# 5_cpu_registers_a.net
KiCad netlist of a schematic drawn in EAGLE
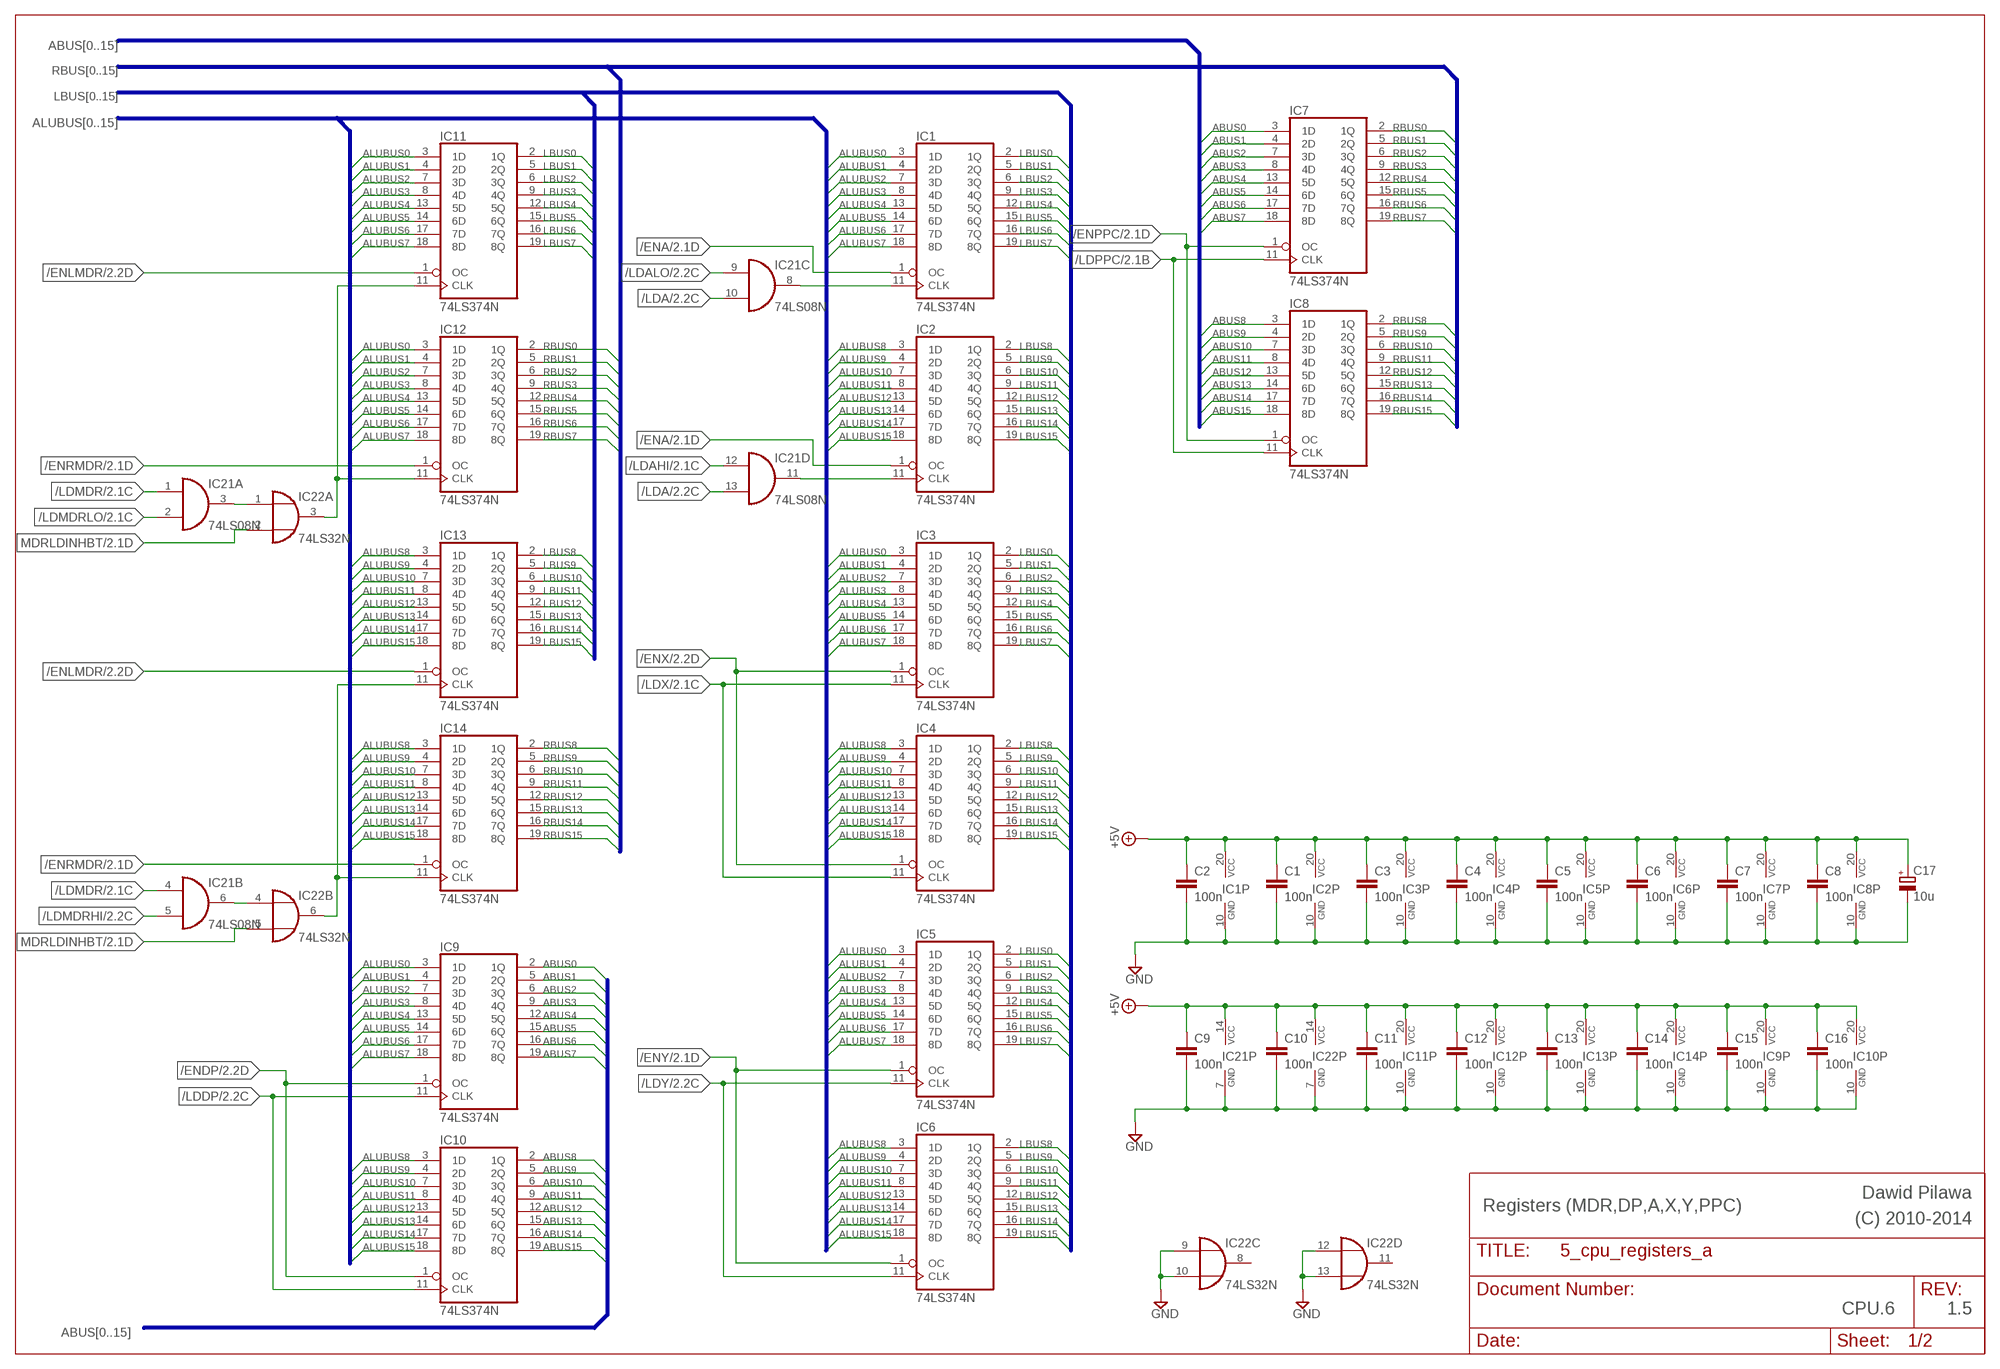
[diagram p0: schematic, sheet 1]
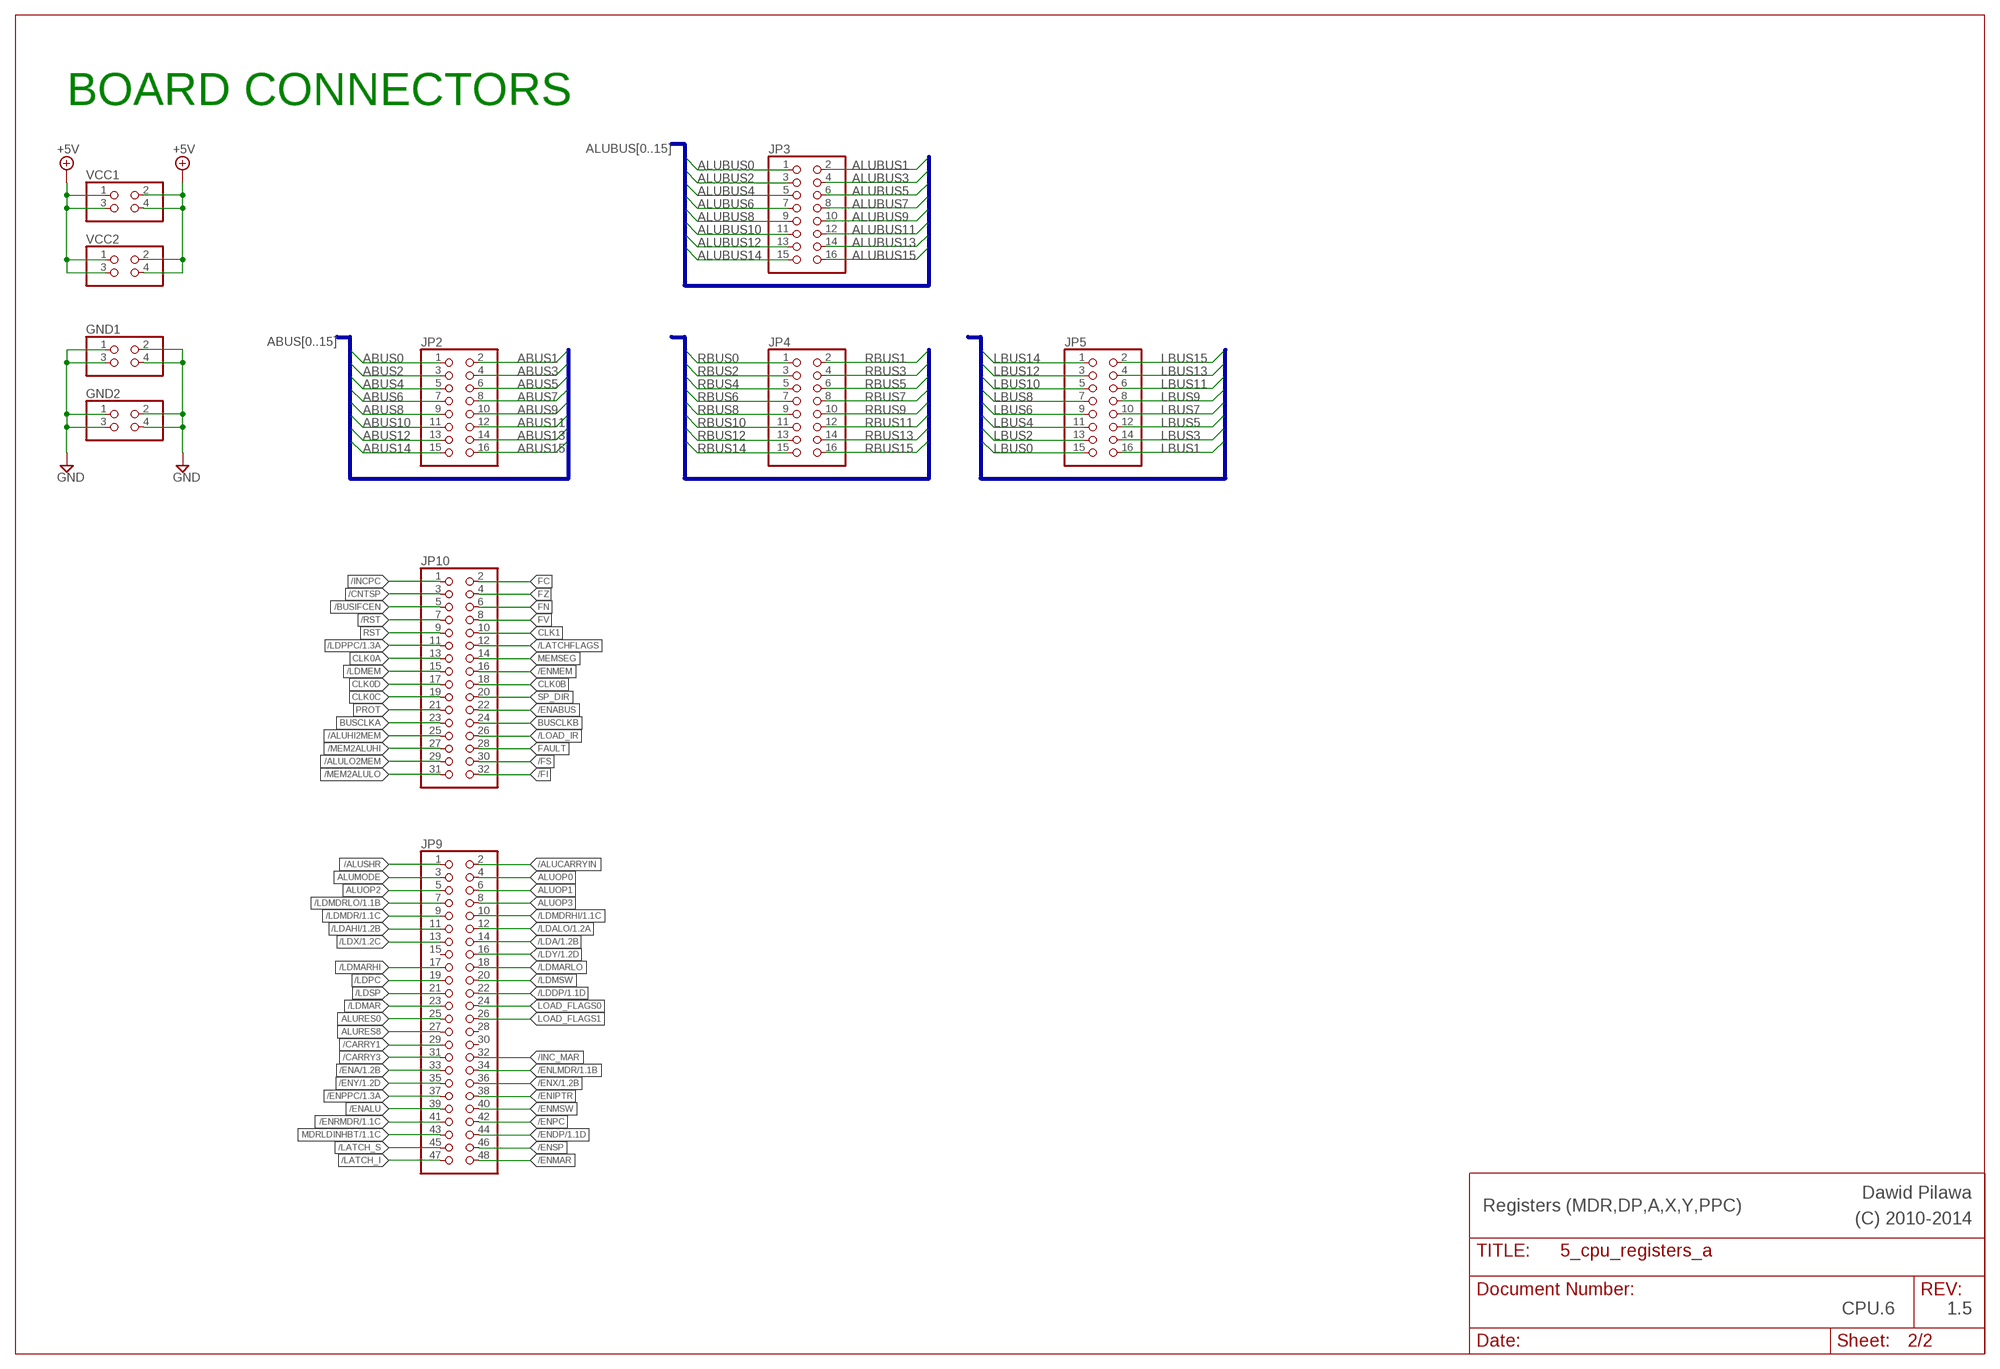
[diagram p1: schematic, sheet 2]

(export (version "E")
  (design (tool "Eeschema 10.0.6"))
  (components
    (comp (ref "GND1")
      (value "PINHD-2X2")
      (footprint "eagle-import:2X02")
      (libsource (lib "eagle-import") (part "PINHD-2X2"))
    )
    (comp (ref "GND2")
      (value "PINHD-2X2")
      (footprint "eagle-import:2X02")
      (libsource (lib "eagle-import") (part "PINHD-2X2"))
    )
    (comp (ref "JP2")
      (value "PINHD-2X8")
      (footprint "eagle-import:2X08")
      (libsource (lib "eagle-import") (part "PINHD-2X8"))
    )
    (comp (ref "JP3")
      (value "PINHD-2X8")
      (footprint "eagle-import:2X08")
      (libsource (lib "eagle-import") (part "PINHD-2X8"))
    )
    (comp (ref "JP4")
      (value "PINHD-2X8")
      (footprint "eagle-import:2X08")
      (libsource (lib "eagle-import") (part "PINHD-2X8"))
    )
    (comp (ref "JP5")
      (value "PINHD-2X8")
      (footprint "eagle-import:2X08")
      (libsource (lib "eagle-import") (part "PINHD-2X8"))
    )
    (comp (ref "JP9")
      (value "PINHD-2X24")
      (footprint "eagle-import:2X24")
      (libsource (lib "eagle-import") (part "PINHD-2X24"))
    )
    (comp (ref "JP10")
      (value "PINHD-2X16")
      (footprint "eagle-import:2X16")
      (libsource (lib "eagle-import") (part "PINHD-2X16"))
    )
    (comp (ref "VCC1")
      (value "PINHD-2X2")
      (footprint "eagle-import:2X02")
      (libsource (lib "eagle-import") (part "PINHD-2X2"))
    )
    (comp (ref "VCC2")
      (value "PINHD-2X2")
      (footprint "eagle-import:2X02")
      (libsource (lib "eagle-import") (part "PINHD-2X2"))
    )
    (comp (ref "C1")
      (value "100n")
      (footprint "eagle-import:C050-024X044")
      (libsource (lib "eagle-import") (part "C-EU050-024X044"))
    )
    (comp (ref "C2")
      (value "100n")
      (footprint "eagle-import:C050-024X044")
      (libsource (lib "eagle-import") (part "C-EU050-024X044"))
    )
    (comp (ref "C3")
      (value "100n")
      (footprint "eagle-import:C050-024X044")
      (libsource (lib "eagle-import") (part "C-EU050-024X044"))
    )
    (comp (ref "C4")
      (value "100n")
      (footprint "eagle-import:C050-024X044")
      (libsource (lib "eagle-import") (part "C-EU050-024X044"))
    )
    (comp (ref "C5")
      (value "100n")
      (footprint "eagle-import:C050-024X044")
      (libsource (lib "eagle-import") (part "C-EU050-024X044"))
    )
    (comp (ref "C6")
      (value "100n")
      (footprint "eagle-import:C050-024X044")
      (libsource (lib "eagle-import") (part "C-EU050-024X044"))
    )
    (comp (ref "C7")
      (value "100n")
      (footprint "eagle-import:C050-024X044")
      (libsource (lib "eagle-import") (part "C-EU050-024X044"))
    )
    (comp (ref "C8")
      (value "100n")
      (footprint "eagle-import:C050-024X044")
      (libsource (lib "eagle-import") (part "C-EU050-024X044"))
    )
    (comp (ref "C9")
      (value "100n")
      (footprint "eagle-import:C050-024X044")
      (libsource (lib "eagle-import") (part "C-EU050-024X044"))
    )
    (comp (ref "C10")
      (value "100n")
      (footprint "eagle-import:C050-024X044")
      (libsource (lib "eagle-import") (part "C-EU050-024X044"))
    )
    (comp (ref "C11")
      (value "100n")
      (footprint "eagle-import:C050-024X044")
      (libsource (lib "eagle-import") (part "C-EU050-024X044"))
    )
    (comp (ref "C12")
      (value "100n")
      (footprint "eagle-import:C050-024X044")
      (libsource (lib "eagle-import") (part "C-EU050-024X044"))
    )
    (comp (ref "C13")
      (value "100n")
      (footprint "eagle-import:C050-024X044")
      (libsource (lib "eagle-import") (part "C-EU050-024X044"))
    )
    (comp (ref "C14")
      (value "100n")
      (footprint "eagle-import:C050-024X044")
      (libsource (lib "eagle-import") (part "C-EU050-024X044"))
    )
    (comp (ref "C15")
      (value "100n")
      (footprint "eagle-import:C050-024X044")
      (libsource (lib "eagle-import") (part "C-EU050-024X044"))
    )
    (comp (ref "C16")
      (value "100n")
      (footprint "eagle-import:C050-024X044")
      (libsource (lib "eagle-import") (part "C-EU050-024X044"))
    )
    (comp (ref "C17")
      (value "10u")
      (footprint "eagle-import:E2,5-6")
      (libsource (lib "eagle-import") (part "CPOL-EUE2.5-6"))
    )
    (comp (ref "IC1")
      (value "74LS374N")
      (footprint "eagle-import:DIL20")
      (libsource (lib "eagle-import") (part "74374NLS"))
    )
    (comp (ref "IC2")
      (value "74LS374N")
      (footprint "eagle-import:DIL20")
      (libsource (lib "eagle-import") (part "74374NLS"))
    )
    (comp (ref "IC3")
      (value "74LS374N")
      (footprint "eagle-import:DIL20")
      (libsource (lib "eagle-import") (part "74374NLS"))
    )
    (comp (ref "IC4")
      (value "74LS374N")
      (footprint "eagle-import:DIL20")
      (libsource (lib "eagle-import") (part "74374NLS"))
    )
    (comp (ref "IC5")
      (value "74LS374N")
      (footprint "eagle-import:DIL20")
      (libsource (lib "eagle-import") (part "74374NLS"))
    )
    (comp (ref "IC6")
      (value "74LS374N")
      (footprint "eagle-import:DIL20")
      (libsource (lib "eagle-import") (part "74374NLS"))
    )
    (comp (ref "IC7")
      (value "74LS374N")
      (footprint "eagle-import:DIL20")
      (libsource (lib "eagle-import") (part "74374NLS"))
    )
    (comp (ref "IC8")
      (value "74LS374N")
      (footprint "eagle-import:DIL20")
      (libsource (lib "eagle-import") (part "74374NLS"))
    )
    (comp (ref "IC9")
      (value "74LS374N")
      (footprint "eagle-import:DIL20")
      (libsource (lib "eagle-import") (part "74374NLS"))
    )
    (comp (ref "IC10")
      (value "74LS374N")
      (footprint "eagle-import:DIL20")
      (libsource (lib "eagle-import") (part "74374NLS"))
    )
    (comp (ref "IC11")
      (value "74LS374N")
      (footprint "eagle-import:DIL20")
      (libsource (lib "eagle-import") (part "74374NLS"))
    )
    (comp (ref "IC12")
      (value "74LS374N")
      (footprint "eagle-import:DIL20")
      (libsource (lib "eagle-import") (part "74374NLS"))
    )
    (comp (ref "IC13")
      (value "74LS374N")
      (footprint "eagle-import:DIL20")
      (libsource (lib "eagle-import") (part "74374NLS"))
    )
    (comp (ref "IC14")
      (value "74LS374N")
      (footprint "eagle-import:DIL20")
      (libsource (lib "eagle-import") (part "74374NLS"))
    )
    (comp (ref "IC21")
      (value "74LS08N")
      (footprint "eagle-import:DIL14")
      (libsource (lib "eagle-import") (part "7408NLS"))
    )
    (comp (ref "IC22")
      (value "74LS32N")
      (footprint "eagle-import:DIL14")
      (libsource (lib "eagle-import") (part "7432NLS"))
    )
  )
  (nets
    (net (code "1") (name "+5V") (class "Default")
      (node (ref "C1") (pin "1") (pinfunction "1_1") (pintype "passive"))
      (node (ref "C10") (pin "1") (pinfunction "1_1") (pintype "passive"))
      (node (ref "C11") (pin "1") (pinfunction "1_1") (pintype "passive"))
      (node (ref "C12") (pin "1") (pinfunction "1_1") (pintype "passive"))
      (node (ref "C13") (pin "1") (pinfunction "1_1") (pintype "passive"))
      (node (ref "C14") (pin "1") (pinfunction "1_1") (pintype "passive"))
      (node (ref "C15") (pin "1") (pinfunction "1_1") (pintype "passive"))
      (node (ref "C16") (pin "1") (pinfunction "1_1") (pintype "passive"))
      (node (ref "C17") (pin "+") (pinfunction "+_+") (pintype "passive"))
      (node (ref "C2") (pin "1") (pinfunction "1_1") (pintype "passive"))
      (node (ref "C3") (pin "1") (pinfunction "1_1") (pintype "passive"))
      (node (ref "C4") (pin "1") (pinfunction "1_1") (pintype "passive"))
      (node (ref "C5") (pin "1") (pinfunction "1_1") (pintype "passive"))
      (node (ref "C6") (pin "1") (pinfunction "1_1") (pintype "passive"))
      (node (ref "C7") (pin "1") (pinfunction "1_1") (pintype "passive"))
      (node (ref "C8") (pin "1") (pinfunction "1_1") (pintype "passive"))
      (node (ref "C9") (pin "1") (pinfunction "1_1") (pintype "passive"))
      (node (ref "IC1") (pin "20") (pinfunction "VCC_20") (pintype "power_in"))
      (node (ref "IC10") (pin "20") (pinfunction "VCC_20") (pintype "power_in"))
      (node (ref "IC11") (pin "20") (pinfunction "VCC_20") (pintype "power_in"))
      (node (ref "IC12") (pin "20") (pinfunction "VCC_20") (pintype "power_in"))
      (node (ref "IC13") (pin "20") (pinfunction "VCC_20") (pintype "power_in"))
      (node (ref "IC14") (pin "20") (pinfunction "VCC_20") (pintype "power_in"))
      (node (ref "IC2") (pin "20") (pinfunction "VCC_20") (pintype "power_in"))
      (node (ref "IC21") (pin "14") (pinfunction "VCC_14") (pintype "power_in"))
      (node (ref "IC22") (pin "14") (pinfunction "VCC_14") (pintype "power_in"))
      (node (ref "IC3") (pin "20") (pinfunction "VCC_20") (pintype "power_in"))
      (node (ref "IC4") (pin "20") (pinfunction "VCC_20") (pintype "power_in"))
      (node (ref "IC5") (pin "20") (pinfunction "VCC_20") (pintype "power_in"))
      (node (ref "IC6") (pin "20") (pinfunction "VCC_20") (pintype "power_in"))
      (node (ref "IC7") (pin "20") (pinfunction "VCC_20") (pintype "power_in"))
      (node (ref "IC8") (pin "20") (pinfunction "VCC_20") (pintype "power_in"))
      (node (ref "IC9") (pin "20") (pinfunction "VCC_20") (pintype "power_in"))
      (node (ref "VCC1") (pin "1") (pinfunction "1_1") (pintype "passive"))
      (node (ref "VCC1") (pin "2") (pinfunction "2_2") (pintype "passive"))
      (node (ref "VCC1") (pin "3") (pinfunction "3_3") (pintype "passive"))
      (node (ref "VCC1") (pin "4") (pinfunction "4_4") (pintype "passive"))
      (node (ref "VCC2") (pin "1") (pinfunction "1_1") (pintype "passive"))
      (node (ref "VCC2") (pin "2") (pinfunction "2_2") (pintype "passive"))
      (node (ref "VCC2") (pin "3") (pinfunction "3_3") (pintype "passive"))
      (node (ref "VCC2") (pin "4") (pinfunction "4_4") (pintype "passive"))
    )
    (net (code "8") (name "ABUS0") (class "Default")
      (node (ref "IC7") (pin "3") (pinfunction "1D_3") (pintype "input"))
      (node (ref "IC9") (pin "2") (pinfunction "1Q_2") (pintype "tri_state"))
      (node (ref "JP2") (pin "1") (pinfunction "1_1") (pintype "passive"))
    )
    (net (code "9") (name "ABUS1") (class "Default")
      (node (ref "IC7") (pin "4") (pinfunction "2D_4") (pintype "input"))
      (node (ref "IC9") (pin "5") (pinfunction "2Q_5") (pintype "tri_state"))
      (node (ref "JP2") (pin "2") (pinfunction "2_2") (pintype "passive"))
    )
    (net (code "10") (name "ABUS2") (class "Default")
      (node (ref "IC7") (pin "7") (pinfunction "3D_7") (pintype "input"))
      (node (ref "IC9") (pin "6") (pinfunction "3Q_6") (pintype "tri_state"))
      (node (ref "JP2") (pin "3") (pinfunction "3_3") (pintype "passive"))
    )
    (net (code "11") (name "ABUS3") (class "Default")
      (node (ref "IC7") (pin "8") (pinfunction "4D_8") (pintype "input"))
      (node (ref "IC9") (pin "9") (pinfunction "4Q_9") (pintype "tri_state"))
      (node (ref "JP2") (pin "4") (pinfunction "4_4") (pintype "passive"))
    )
    (net (code "12") (name "ABUS4") (class "Default")
      (node (ref "IC7") (pin "13") (pinfunction "5D_13") (pintype "input"))
      (node (ref "IC9") (pin "12") (pinfunction "5Q_12") (pintype "tri_state"))
      (node (ref "JP2") (pin "5") (pinfunction "5_5") (pintype "passive"))
    )
    (net (code "13") (name "ABUS5") (class "Default")
      (node (ref "IC7") (pin "14") (pinfunction "6D_14") (pintype "input"))
      (node (ref "IC9") (pin "15") (pinfunction "6Q_15") (pintype "tri_state"))
      (node (ref "JP2") (pin "6") (pinfunction "6_6") (pintype "passive"))
    )
    (net (code "14") (name "ABUS6") (class "Default")
      (node (ref "IC7") (pin "17") (pinfunction "7D_17") (pintype "input"))
      (node (ref "IC9") (pin "16") (pinfunction "7Q_16") (pintype "tri_state"))
      (node (ref "JP2") (pin "7") (pinfunction "7_7") (pintype "passive"))
    )
    (net (code "15") (name "ABUS7") (class "Default")
      (node (ref "IC7") (pin "18") (pinfunction "8D_18") (pintype "input"))
      (node (ref "IC9") (pin "19") (pinfunction "8Q_19") (pintype "tri_state"))
      (node (ref "JP2") (pin "8") (pinfunction "8_8") (pintype "passive"))
    )
    (net (code "16") (name "ABUS8") (class "Default")
      (node (ref "IC10") (pin "2") (pinfunction "1Q_2") (pintype "tri_state"))
      (node (ref "IC8") (pin "3") (pinfunction "1D_3") (pintype "input"))
      (node (ref "JP2") (pin "9") (pinfunction "9_9") (pintype "passive"))
    )
    (net (code "17") (name "ABUS9") (class "Default")
      (node (ref "IC10") (pin "5") (pinfunction "2Q_5") (pintype "tri_state"))
      (node (ref "IC8") (pin "4") (pinfunction "2D_4") (pintype "input"))
      (node (ref "JP2") (pin "10") (pinfunction "10_10") (pintype "passive"))
    )
    (net (code "18") (name "ABUS10") (class "Default")
      (node (ref "IC10") (pin "6") (pinfunction "3Q_6") (pintype "tri_state"))
      (node (ref "IC8") (pin "7") (pinfunction "3D_7") (pintype "input"))
      (node (ref "JP2") (pin "11") (pinfunction "11_11") (pintype "passive"))
    )
    (net (code "19") (name "ABUS11") (class "Default")
      (node (ref "IC10") (pin "9") (pinfunction "4Q_9") (pintype "tri_state"))
      (node (ref "IC8") (pin "8") (pinfunction "4D_8") (pintype "input"))
      (node (ref "JP2") (pin "12") (pinfunction "12_12") (pintype "passive"))
    )
    (net (code "20") (name "ABUS12") (class "Default")
      (node (ref "IC10") (pin "12") (pinfunction "5Q_12") (pintype "tri_state"))
      (node (ref "IC8") (pin "13") (pinfunction "5D_13") (pintype "input"))
      (node (ref "JP2") (pin "13") (pinfunction "13_13") (pintype "passive"))
    )
    (net (code "21") (name "ABUS13") (class "Default")
      (node (ref "IC10") (pin "15") (pinfunction "6Q_15") (pintype "tri_state"))
      (node (ref "IC8") (pin "14") (pinfunction "6D_14") (pintype "input"))
      (node (ref "JP2") (pin "14") (pinfunction "14_14") (pintype "passive"))
    )
    (net (code "22") (name "ABUS14") (class "Default")
      (node (ref "IC10") (pin "16") (pinfunction "7Q_16") (pintype "tri_state"))
      (node (ref "IC8") (pin "17") (pinfunction "7D_17") (pintype "input"))
      (node (ref "JP2") (pin "15") (pinfunction "15_15") (pintype "passive"))
    )
    (net (code "23") (name "ABUS15") (class "Default")
      (node (ref "IC10") (pin "19") (pinfunction "8Q_19") (pintype "tri_state"))
      (node (ref "IC8") (pin "18") (pinfunction "8D_18") (pintype "input"))
      (node (ref "JP2") (pin "16") (pinfunction "16_16") (pintype "passive"))
    )
    (net (code "24") (name "ALUBUS0") (class "Default")
      (node (ref "IC1") (pin "3") (pinfunction "1D_3") (pintype "input"))
      (node (ref "IC11") (pin "3") (pinfunction "1D_3") (pintype "input"))
      (node (ref "IC12") (pin "3") (pinfunction "1D_3") (pintype "input"))
      (node (ref "IC3") (pin "3") (pinfunction "1D_3") (pintype "input"))
      (node (ref "IC5") (pin "3") (pinfunction "1D_3") (pintype "input"))
      (node (ref "IC9") (pin "3") (pinfunction "1D_3") (pintype "input"))
      (node (ref "JP3") (pin "1") (pinfunction "1_1") (pintype "passive"))
    )
    (net (code "25") (name "ALUBUS1") (class "Default")
      (node (ref "IC1") (pin "4") (pinfunction "2D_4") (pintype "input"))
      (node (ref "IC11") (pin "4") (pinfunction "2D_4") (pintype "input"))
      (node (ref "IC12") (pin "4") (pinfunction "2D_4") (pintype "input"))
      (node (ref "IC3") (pin "4") (pinfunction "2D_4") (pintype "input"))
      (node (ref "IC5") (pin "4") (pinfunction "2D_4") (pintype "input"))
      (node (ref "IC9") (pin "4") (pinfunction "2D_4") (pintype "input"))
      (node (ref "JP3") (pin "2") (pinfunction "2_2") (pintype "passive"))
    )
    (net (code "26") (name "ALUBUS2") (class "Default")
      (node (ref "IC1") (pin "7") (pinfunction "3D_7") (pintype "input"))
      (node (ref "IC11") (pin "7") (pinfunction "3D_7") (pintype "input"))
      (node (ref "IC12") (pin "7") (pinfunction "3D_7") (pintype "input"))
      (node (ref "IC3") (pin "7") (pinfunction "3D_7") (pintype "input"))
      (node (ref "IC5") (pin "7") (pinfunction "3D_7") (pintype "input"))
      (node (ref "IC9") (pin "7") (pinfunction "3D_7") (pintype "input"))
      (node (ref "JP3") (pin "3") (pinfunction "3_3") (pintype "passive"))
    )
    (net (code "27") (name "ALUBUS3") (class "Default")
      (node (ref "IC1") (pin "8") (pinfunction "4D_8") (pintype "input"))
      (node (ref "IC11") (pin "8") (pinfunction "4D_8") (pintype "input"))
      (node (ref "IC12") (pin "8") (pinfunction "4D_8") (pintype "input"))
      (node (ref "IC3") (pin "8") (pinfunction "4D_8") (pintype "input"))
      (node (ref "IC5") (pin "8") (pinfunction "4D_8") (pintype "input"))
      (node (ref "IC9") (pin "8") (pinfunction "4D_8") (pintype "input"))
      (node (ref "JP3") (pin "4") (pinfunction "4_4") (pintype "passive"))
    )
    (net (code "28") (name "ALUBUS4") (class "Default")
      (node (ref "IC1") (pin "13") (pinfunction "5D_13") (pintype "input"))
      (node (ref "IC11") (pin "13") (pinfunction "5D_13") (pintype "input"))
      (node (ref "IC12") (pin "13") (pinfunction "5D_13") (pintype "input"))
      (node (ref "IC3") (pin "13") (pinfunction "5D_13") (pintype "input"))
      (node (ref "IC5") (pin "13") (pinfunction "5D_13") (pintype "input"))
      (node (ref "IC9") (pin "13") (pinfunction "5D_13") (pintype "input"))
      (node (ref "JP3") (pin "5") (pinfunction "5_5") (pintype "passive"))
    )
    (net (code "29") (name "ALUBUS5") (class "Default")
      (node (ref "IC1") (pin "14") (pinfunction "6D_14") (pintype "input"))
      (node (ref "IC11") (pin "14") (pinfunction "6D_14") (pintype "input"))
      (node (ref "IC12") (pin "14") (pinfunction "6D_14") (pintype "input"))
      (node (ref "IC3") (pin "14") (pinfunction "6D_14") (pintype "input"))
      (node (ref "IC5") (pin "14") (pinfunction "6D_14") (pintype "input"))
      (node (ref "IC9") (pin "14") (pinfunction "6D_14") (pintype "input"))
      (node (ref "JP3") (pin "6") (pinfunction "6_6") (pintype "passive"))
    )
    (net (code "30") (name "ALUBUS6") (class "Default")
      (node (ref "IC1") (pin "17") (pinfunction "7D_17") (pintype "input"))
      (node (ref "IC11") (pin "17") (pinfunction "7D_17") (pintype "input"))
      (node (ref "IC12") (pin "17") (pinfunction "7D_17") (pintype "input"))
      (node (ref "IC3") (pin "17") (pinfunction "7D_17") (pintype "input"))
      (node (ref "IC5") (pin "17") (pinfunction "7D_17") (pintype "input"))
      (node (ref "IC9") (pin "17") (pinfunction "7D_17") (pintype "input"))
      (node (ref "JP3") (pin "7") (pinfunction "7_7") (pintype "passive"))
    )
    (net (code "31") (name "ALUBUS7") (class "Default")
      (node (ref "IC1") (pin "18") (pinfunction "8D_18") (pintype "input"))
      (node (ref "IC11") (pin "18") (pinfunction "8D_18") (pintype "input"))
      (node (ref "IC12") (pin "18") (pinfunction "8D_18") (pintype "input"))
      (node (ref "IC3") (pin "18") (pinfunction "8D_18") (pintype "input"))
      (node (ref "IC5") (pin "18") (pinfunction "8D_18") (pintype "input"))
      (node (ref "IC9") (pin "18") (pinfunction "8D_18") (pintype "input"))
      (node (ref "JP3") (pin "8") (pinfunction "8_8") (pintype "passive"))
    )
    (net (code "32") (name "ALUBUS8") (class "Default")
      (node (ref "IC10") (pin "3") (pinfunction "1D_3") (pintype "input"))
      (node (ref "IC13") (pin "3") (pinfunction "1D_3") (pintype "input"))
      (node (ref "IC14") (pin "3") (pinfunction "1D_3") (pintype "input"))
      (node (ref "IC2") (pin "3") (pinfunction "1D_3") (pintype "input"))
      (node (ref "IC4") (pin "3") (pinfunction "1D_3") (pintype "input"))
      (node (ref "IC6") (pin "3") (pinfunction "1D_3") (pintype "input"))
      (node (ref "JP3") (pin "9") (pinfunction "9_9") (pintype "passive"))
    )
    (net (code "33") (name "ALUBUS9") (class "Default")
      (node (ref "IC10") (pin "4") (pinfunction "2D_4") (pintype "input"))
      (node (ref "IC13") (pin "4") (pinfunction "2D_4") (pintype "input"))
      (node (ref "IC14") (pin "4") (pinfunction "2D_4") (pintype "input"))
      (node (ref "IC2") (pin "4") (pinfunction "2D_4") (pintype "input"))
      (node (ref "IC4") (pin "4") (pinfunction "2D_4") (pintype "input"))
      (node (ref "IC6") (pin "4") (pinfunction "2D_4") (pintype "input"))
      (node (ref "JP3") (pin "10") (pinfunction "10_10") (pintype "passive"))
    )
    (net (code "34") (name "ALUBUS10") (class "Default")
      (node (ref "IC10") (pin "7") (pinfunction "3D_7") (pintype "input"))
      (node (ref "IC13") (pin "7") (pinfunction "3D_7") (pintype "input"))
      (node (ref "IC14") (pin "7") (pinfunction "3D_7") (pintype "input"))
      (node (ref "IC2") (pin "7") (pinfunction "3D_7") (pintype "input"))
      (node (ref "IC4") (pin "7") (pinfunction "3D_7") (pintype "input"))
      (node (ref "IC6") (pin "7") (pinfunction "3D_7") (pintype "input"))
      (node (ref "JP3") (pin "11") (pinfunction "11_11") (pintype "passive"))
    )
    (net (code "35") (name "ALUBUS11") (class "Default")
      (node (ref "IC10") (pin "8") (pinfunction "4D_8") (pintype "input"))
      (node (ref "IC13") (pin "8") (pinfunction "4D_8") (pintype "input"))
      (node (ref "IC14") (pin "8") (pinfunction "4D_8") (pintype "input"))
      (node (ref "IC2") (pin "8") (pinfunction "4D_8") (pintype "input"))
      (node (ref "IC4") (pin "8") (pinfunction "4D_8") (pintype "input"))
      (node (ref "IC6") (pin "8") (pinfunction "4D_8") (pintype "input"))
      (node (ref "JP3") (pin "12") (pinfunction "12_12") (pintype "passive"))
    )
    (net (code "36") (name "ALUBUS12") (class "Default")
      (node (ref "IC10") (pin "13") (pinfunction "5D_13") (pintype "input"))
      (node (ref "IC13") (pin "13") (pinfunction "5D_13") (pintype "input"))
      (node (ref "IC14") (pin "13") (pinfunction "5D_13") (pintype "input"))
      (node (ref "IC2") (pin "13") (pinfunction "5D_13") (pintype "input"))
      (node (ref "IC4") (pin "13") (pinfunction "5D_13") (pintype "input"))
      (node (ref "IC6") (pin "13") (pinfunction "5D_13") (pintype "input"))
      (node (ref "JP3") (pin "13") (pinfunction "13_13") (pintype "passive"))
    )
    (net (code "37") (name "ALUBUS13") (class "Default")
      (node (ref "IC10") (pin "14") (pinfunction "6D_14") (pintype "input"))
      (node (ref "IC13") (pin "14") (pinfunction "6D_14") (pintype "input"))
      (node (ref "IC14") (pin "14") (pinfunction "6D_14") (pintype "input"))
      (node (ref "IC2") (pin "14") (pinfunction "6D_14") (pintype "input"))
      (node (ref "IC4") (pin "14") (pinfunction "6D_14") (pintype "input"))
      (node (ref "IC6") (pin "14") (pinfunction "6D_14") (pintype "input"))
      (node (ref "JP3") (pin "14") (pinfunction "14_14") (pintype "passive"))
    )
    (net (code "38") (name "ALUBUS14") (class "Default")
      (node (ref "IC10") (pin "17") (pinfunction "7D_17") (pintype "input"))
      (node (ref "IC13") (pin "17") (pinfunction "7D_17") (pintype "input"))
      (node (ref "IC14") (pin "17") (pinfunction "7D_17") (pintype "input"))
      (node (ref "IC2") (pin "17") (pinfunction "7D_17") (pintype "input"))
      (node (ref "IC4") (pin "17") (pinfunction "7D_17") (pintype "input"))
      (node (ref "IC6") (pin "17") (pinfunction "7D_17") (pintype "input"))
      (node (ref "JP3") (pin "15") (pinfunction "15_15") (pintype "passive"))
    )
    (net (code "39") (name "ALUBUS15") (class "Default")
      (node (ref "IC10") (pin "18") (pinfunction "8D_18") (pintype "input"))
      (node (ref "IC13") (pin "18") (pinfunction "8D_18") (pintype "input"))
      (node (ref "IC14") (pin "18") (pinfunction "8D_18") (pintype "input"))
      (node (ref "IC2") (pin "18") (pinfunction "8D_18") (pintype "input"))
      (node (ref "IC4") (pin "18") (pinfunction "8D_18") (pintype "input"))
      (node (ref "IC6") (pin "18") (pinfunction "8D_18") (pintype "input"))
      (node (ref "JP3") (pin "16") (pinfunction "16_16") (pintype "passive"))
    )
    (net (code "40") (name "ALUMODE") (class "Default")
      (node (ref "JP9") (pin "3") (pinfunction "3_3") (pintype "passive"))
    )
    (net (code "41") (name "ALUOP0") (class "Default")
      (node (ref "JP9") (pin "4") (pinfunction "4_4") (pintype "passive"))
    )
    (net (code "42") (name "ALUOP1") (class "Default")
      (node (ref "JP9") (pin "6") (pinfunction "6_6") (pintype "passive"))
    )
    (net (code "43") (name "ALUOP2") (class "Default")
      (node (ref "JP9") (pin "5") (pinfunction "5_5") (pintype "passive"))
    )
    (net (code "44") (name "ALUOP3") (class "Default")
      (node (ref "JP9") (pin "8") (pinfunction "8_8") (pintype "passive"))
    )
    (net (code "45") (name "ALURES0") (class "Default")
      (node (ref "JP9") (pin "25") (pinfunction "25_25") (pintype "passive"))
    )
    (net (code "46") (name "ALURES8") (class "Default")
      (node (ref "JP9") (pin "27") (pinfunction "27_27") (pintype "passive"))
    )
    (net (code "47") (name "BUSCLKA") (class "Default")
      (node (ref "JP10") (pin "23") (pinfunction "23_23") (pintype "passive"))
    )
    (net (code "48") (name "BUSCLKB") (class "Default")
      (node (ref "JP10") (pin "24") (pinfunction "24_24") (pintype "passive"))
    )
    (net (code "49") (name "CLK0A") (class "Default")
      (node (ref "JP10") (pin "13") (pinfunction "13_13") (pintype "passive"))
    )
    (net (code "50") (name "CLK0B") (class "Default")
      (node (ref "JP10") (pin "18") (pinfunction "18_18") (pintype "passive"))
    )
    (net (code "51") (name "CLK0C") (class "Default")
      (node (ref "JP10") (pin "19") (pinfunction "19_19") (pintype "passive"))
    )
    (net (code "52") (name "CLK0D") (class "Default")
      (node (ref "JP10") (pin "17") (pinfunction "17_17") (pintype "passive"))
    )
    (net (code "53") (name "CLK1") (class "Default")
      (node (ref "JP10") (pin "10") (pinfunction "10_10") (pintype "passive"))
    )
    (net (code "54") (name "FAULT") (class "Default")
      (node (ref "JP10") (pin "28") (pinfunction "28_28") (pintype "passive"))
    )
    (net (code "55") (name "FC") (class "Default")
      (node (ref "JP10") (pin "2") (pinfunction "2_2") (pintype "passive"))
    )
    (net (code "56") (name "FN") (class "Default")
      (node (ref "JP10") (pin "6") (pinfunction "6_6") (pintype "passive"))
    )
    (net (code "57") (name "FV") (class "Default")
      (node (ref "JP10") (pin "8") (pinfunction "8_8") (pintype "passive"))
    )
    (net (code "58") (name "FZ") (class "Default")
      (node (ref "JP10") (pin "4") (pinfunction "4_4") (pintype "passive"))
    )
    (net (code "59") (name "GND") (class "Default")
      (node (ref "C1") (pin "2") (pinfunction "2_2") (pintype "passive"))
      (node (ref "C10") (pin "2") (pinfunction "2_2") (pintype "passive"))
      (node (ref "C11") (pin "2") (pinfunction "2_2") (pintype "passive"))
      (node (ref "C12") (pin "2") (pinfunction "2_2") (pintype "passive"))
      (node (ref "C13") (pin "2") (pinfunction "2_2") (pintype "passive"))
      (node (ref "C14") (pin "2") (pinfunction "2_2") (pintype "passive"))
      (node (ref "C15") (pin "2") (pinfunction "2_2") (pintype "passive"))
      (node (ref "C16") (pin "2") (pinfunction "2_2") (pintype "passive"))
      (node (ref "C17") (pin "-") (pinfunction "-_-") (pintype "passive"))
      (node (ref "C2") (pin "2") (pinfunction "2_2") (pintype "passive"))
      (node (ref "C3") (pin "2") (pinfunction "2_2") (pintype "passive"))
      (node (ref "C4") (pin "2") (pinfunction "2_2") (pintype "passive"))
      (node (ref "C5") (pin "2") (pinfunction "2_2") (pintype "passive"))
      (node (ref "C6") (pin "2") (pinfunction "2_2") (pintype "passive"))
      (node (ref "C7") (pin "2") (pinfunction "2_2") (pintype "passive"))
      (node (ref "C8") (pin "2") (pinfunction "2_2") (pintype "passive"))
      (node (ref "C9") (pin "2") (pinfunction "2_2") (pintype "passive"))
      (node (ref "GND1") (pin "1") (pinfunction "1_1") (pintype "passive"))
      (node (ref "GND1") (pin "2") (pinfunction "2_2") (pintype "passive"))
      (node (ref "GND1") (pin "3") (pinfunction "3_3") (pintype "passive"))
      (node (ref "GND1") (pin "4") (pinfunction "4_4") (pintype "passive"))
      (node (ref "GND2") (pin "1") (pinfunction "1_1") (pintype "passive"))
      (node (ref "GND2") (pin "2") (pinfunction "2_2") (pintype "passive"))
      (node (ref "GND2") (pin "3") (pinfunction "3_3") (pintype "passive"))
      (node (ref "GND2") (pin "4") (pinfunction "4_4") (pintype "passive"))
      (node (ref "IC1") (pin "10") (pinfunction "GND_10") (pintype "power_in"))
      (node (ref "IC10") (pin "10") (pinfunction "GND_10") (pintype "power_in"))
      (node (ref "IC11") (pin "10") (pinfunction "GND_10") (pintype "power_in"))
      (node (ref "IC12") (pin "10") (pinfunction "GND_10") (pintype "power_in"))
      (node (ref "IC13") (pin "10") (pinfunction "GND_10") (pintype "power_in"))
      (node (ref "IC14") (pin "10") (pinfunction "GND_10") (pintype "power_in"))
      (node (ref "IC2") (pin "10") (pinfunction "GND_10") (pintype "power_in"))
      (node (ref "IC21") (pin "7") (pinfunction "GND_7") (pintype "power_in"))
      (node (ref "IC22") (pin "10") (pinfunction "I1_10") (pintype "input"))
      (node (ref "IC22") (pin "12") (pinfunction "I0_12") (pintype "input"))
      (node (ref "IC22") (pin "13") (pinfunction "I1_13") (pintype "input"))
      (node (ref "IC22") (pin "7") (pinfunction "GND_7") (pintype "power_in"))
      (node (ref "IC22") (pin "9") (pinfunction "I0_9") (pintype "input"))
      (node (ref "IC3") (pin "10") (pinfunction "GND_10") (pintype "power_in"))
      (node (ref "IC4") (pin "10") (pinfunction "GND_10") (pintype "power_in"))
      (node (ref "IC5") (pin "10") (pinfunction "GND_10") (pintype "power_in"))
      (node (ref "IC6") (pin "10") (pinfunction "GND_10") (pintype "power_in"))
      (node (ref "IC7") (pin "10") (pinfunction "GND_10") (pintype "power_in"))
      (node (ref "IC8") (pin "10") (pinfunction "GND_10") (pintype "power_in"))
      (node (ref "IC9") (pin "10") (pinfunction "GND_10") (pintype "power_in"))
    )
    (net (code "60") (name "LBUS0") (class "Default")
      (node (ref "IC1") (pin "2") (pinfunction "1Q_2") (pintype "tri_state"))
      (node (ref "IC11") (pin "2") (pinfunction "1Q_2") (pintype "tri_state"))
      (node (ref "IC3") (pin "2") (pinfunction "1Q_2") (pintype "tri_state"))
      (node (ref "IC5") (pin "2") (pinfunction "1Q_2") (pintype "tri_state"))
      (node (ref "JP5") (pin "15") (pinfunction "15_15") (pintype "passive"))
    )
    (net (code "61") (name "LBUS1") (class "Default")
      (node (ref "IC1") (pin "5") (pinfunction "2Q_5") (pintype "tri_state"))
      (node (ref "IC11") (pin "5") (pinfunction "2Q_5") (pintype "tri_state"))
      (node (ref "IC3") (pin "5") (pinfunction "2Q_5") (pintype "tri_state"))
      (node (ref "IC5") (pin "5") (pinfunction "2Q_5") (pintype "tri_state"))
      (node (ref "JP5") (pin "16") (pinfunction "16_16") (pintype "passive"))
    )
    (net (code "62") (name "LBUS2") (class "Default")
      (node (ref "IC1") (pin "6") (pinfunction "3Q_6") (pintype "tri_state"))
      (node (ref "IC11") (pin "6") (pinfunction "3Q_6") (pintype "tri_state"))
      (node (ref "IC3") (pin "6") (pinfunction "3Q_6") (pintype "tri_state"))
      (node (ref "IC5") (pin "6") (pinfunction "3Q_6") (pintype "tri_state"))
      (node (ref "JP5") (pin "13") (pinfunction "13_13") (pintype "passive"))
    )
    (net (code "63") (name "LBUS3") (class "Default")
      (node (ref "IC1") (pin "9") (pinfunction "4Q_9") (pintype "tri_state"))
      (node (ref "IC11") (pin "9") (pinfunction "4Q_9") (pintype "tri_state"))
      (node (ref "IC3") (pin "9") (pinfunction "4Q_9") (pintype "tri_state"))
      (node (ref "IC5") (pin "9") (pinfunction "4Q_9") (pintype "tri_state"))
      (node (ref "JP5") (pin "14") (pinfunction "14_14") (pintype "passive"))
    )
    (net (code "64") (name "LBUS4") (class "Default")
      (node (ref "IC1") (pin "12") (pinfunction "5Q_12") (pintype "tri_state"))
      (node (ref "IC11") (pin "12") (pinfunction "5Q_12") (pintype "tri_state"))
      (node (ref "IC3") (pin "12") (pinfunction "5Q_12") (pintype "tri_state"))
      (node (ref "IC5") (pin "12") (pinfunction "5Q_12") (pintype "tri_state"))
      (node (ref "JP5") (pin "11") (pinfunction "11_11") (pintype "passive"))
    )
    (net (code "65") (name "LBUS5") (class "Default")
      (node (ref "IC1") (pin "15") (pinfunction "6Q_15") (pintype "tri_state"))
      (node (ref "IC11") (pin "15") (pinfunction "6Q_15") (pintype "tri_state"))
      (node (ref "IC3") (pin "15") (pinfunction "6Q_15") (pintype "tri_state"))
      (node (ref "IC5") (pin "15") (pinfunction "6Q_15") (pintype "tri_state"))
      (node (ref "JP5") (pin "12") (pinfunction "12_12") (pintype "passive"))
    )
    (net (code "66") (name "LBUS6") (class "Default")
      (node (ref "IC1") (pin "16") (pinfunction "7Q_16") (pintype "tri_state"))
      (node (ref "IC11") (pin "16") (pinfunction "7Q_16") (pintype "tri_state"))
      (node (ref "IC3") (pin "16") (pinfunction "7Q_16") (pintype "tri_state"))
      (node (ref "IC5") (pin "16") (pinfunction "7Q_16") (pintype "tri_state"))
      (node (ref "JP5") (pin "9") (pinfunction "9_9") (pintype "passive"))
    )
    (net (code "67") (name "LBUS7") (class "Default")
      (node (ref "IC1") (pin "19") (pinfunction "8Q_19") (pintype "tri_state"))
      (node (ref "IC11") (pin "19") (pinfunction "8Q_19") (pintype "tri_state"))
      (node (ref "IC3") (pin "19") (pinfunction "8Q_19") (pintype "tri_state"))
      (node (ref "IC5") (pin "19") (pinfunction "8Q_19") (pintype "tri_state"))
      (node (ref "JP5") (pin "10") (pinfunction "10_10") (pintype "passive"))
    )
    (net (code "68") (name "LBUS8") (class "Default")
      (node (ref "IC13") (pin "2") (pinfunction "1Q_2") (pintype "tri_state"))
      (node (ref "IC2") (pin "2") (pinfunction "1Q_2") (pintype "tri_state"))
      (node (ref "IC4") (pin "2") (pinfunction "1Q_2") (pintype "tri_state"))
      (node (ref "IC6") (pin "2") (pinfunction "1Q_2") (pintype "tri_state"))
      (node (ref "JP5") (pin "7") (pinfunction "7_7") (pintype "passive"))
    )
    (net (code "69") (name "LBUS9") (class "Default")
      (node (ref "IC13") (pin "5") (pinfunction "2Q_5") (pintype "tri_state"))
      (node (ref "IC2") (pin "5") (pinfunction "2Q_5") (pintype "tri_state"))
      (node (ref "IC4") (pin "5") (pinfunction "2Q_5") (pintype "tri_state"))
      (node (ref "IC6") (pin "5") (pinfunction "2Q_5") (pintype "tri_state"))
      (node (ref "JP5") (pin "8") (pinfunction "8_8") (pintype "passive"))
    )
    (net (code "70") (name "LBUS10") (class "Default")
      (node (ref "IC13") (pin "6") (pinfunction "3Q_6") (pintype "tri_state"))
      (node (ref "IC2") (pin "6") (pinfunction "3Q_6") (pintype "tri_state"))
      (node (ref "IC4") (pin "6") (pinfunction "3Q_6") (pintype "tri_state"))
      (node (ref "IC6") (pin "6") (pinfunction "3Q_6") (pintype "tri_state"))
      (node (ref "JP5") (pin "5") (pinfunction "5_5") (pintype "passive"))
    )
    (net (code "71") (name "LBUS11") (class "Default")
      (node (ref "IC13") (pin "9") (pinfunction "4Q_9") (pintype "tri_state"))
      (node (ref "IC2") (pin "9") (pinfunction "4Q_9") (pintype "tri_state"))
      (node (ref "IC4") (pin "9") (pinfunction "4Q_9") (pintype "tri_state"))
      (node (ref "IC6") (pin "9") (pinfunction "4Q_9") (pintype "tri_state"))
      (node (ref "JP5") (pin "6") (pinfunction "6_6") (pintype "passive"))
    )
    (net (code "72") (name "LBUS12") (class "Default")
      (node (ref "IC13") (pin "12") (pinfunction "5Q_12") (pintype "tri_state"))
      (node (ref "IC2") (pin "12") (pinfunction "5Q_12") (pintype "tri_state"))
      (node (ref "IC4") (pin "12") (pinfunction "5Q_12") (pintype "tri_state"))
      (node (ref "IC6") (pin "12") (pinfunction "5Q_12") (pintype "tri_state"))
      (node (ref "JP5") (pin "3") (pinfunction "3_3") (pintype "passive"))
    )
    (net (code "73") (name "LBUS13") (class "Default")
      (node (ref "IC13") (pin "15") (pinfunction "6Q_15") (pintype "tri_state"))
      (node (ref "IC2") (pin "15") (pinfunction "6Q_15") (pintype "tri_state"))
      (node (ref "IC4") (pin "15") (pinfunction "6Q_15") (pintype "tri_state"))
      (node (ref "IC6") (pin "15") (pinfunction "6Q_15") (pintype "tri_state"))
      (node (ref "JP5") (pin "4") (pinfunction "4_4") (pintype "passive"))
    )
    (net (code "74") (name "LBUS14") (class "Default")
      (node (ref "IC13") (pin "16") (pinfunction "7Q_16") (pintype "tri_state"))
      (node (ref "IC2") (pin "16") (pinfunction "7Q_16") (pintype "tri_state"))
      (node (ref "IC4") (pin "16") (pinfunction "7Q_16") (pintype "tri_state"))
      (node (ref "IC6") (pin "16") (pinfunction "7Q_16") (pintype "tri_state"))
      (node (ref "JP5") (pin "1") (pinfunction "1_1") (pintype "passive"))
    )
    (net (code "75") (name "LBUS15") (class "Default")
      (node (ref "IC13") (pin "19") (pinfunction "8Q_19") (pintype "tri_state"))
      (node (ref "IC2") (pin "19") (pinfunction "8Q_19") (pintype "tri_state"))
      (node (ref "IC4") (pin "19") (pinfunction "8Q_19") (pintype "tri_state"))
      (node (ref "IC6") (pin "19") (pinfunction "8Q_19") (pintype "tri_state"))
      (node (ref "JP5") (pin "2") (pinfunction "2_2") (pintype "passive"))
    )
    (net (code "76") (name "LOAD_FLAGS0") (class "Default")
      (node (ref "JP9") (pin "24") (pinfunction "24_24") (pintype "passive"))
    )
    (net (code "77") (name "LOAD_FLAGS1") (class "Default")
      (node (ref "JP9") (pin "26") (pinfunction "26_26") (pintype "passive"))
    )
    (net (code "78") (name "MDRLDINHBT") (class "Default")
      (node (ref "IC22") (pin "2") (pinfunction "I1_2") (pintype "input"))
      (node (ref "IC22") (pin "5") (pinfunction "I1_5") (pintype "input"))
      (node (ref "JP9") (pin "43") (pinfunction "43_43") (pintype "passive"))
    )
    (net (code "79") (name "MEMSEG") (class "Default")
      (node (ref "JP10") (pin "14") (pinfunction "14_14") (pintype "passive"))
    )
    (net (code "80") (name "Net-(IC1A-CLK)") (class "Default")
      (node (ref "IC1") (pin "11") (pinfunction "CLK_11") (pintype "input"))
      (node (ref "IC21") (pin "8") (pinfunction "O_8") (pintype "output"))
    )
    (net (code "81") (name "Net-(IC11A-CLK)") (class "Default")
      (node (ref "IC11") (pin "11") (pinfunction "CLK_11") (pintype "input"))
      (node (ref "IC12") (pin "11") (pinfunction "CLK_11") (pintype "input"))
      (node (ref "IC22") (pin "3") (pinfunction "O_3") (pintype "output"))
    )
    (net (code "82") (name "Net-(IC13A-CLK)") (class "Default")
      (node (ref "IC13") (pin "11") (pinfunction "CLK_11") (pintype "input"))
      (node (ref "IC14") (pin "11") (pinfunction "CLK_11") (pintype "input"))
      (node (ref "IC22") (pin "6") (pinfunction "O_6") (pintype "output"))
    )
    (net (code "83") (name "Net-(IC21A-O)") (class "Default")
      (node (ref "IC21") (pin "3") (pinfunction "O_3") (pintype "output"))
      (node (ref "IC22") (pin "1") (pinfunction "I0_1") (pintype "input"))
    )
    (net (code "84") (name "Net-(IC21B-O)") (class "Default")
      (node (ref "IC21") (pin "6") (pinfunction "O_6") (pintype "output"))
      (node (ref "IC22") (pin "4") (pinfunction "I0_4") (pintype "input"))
    )
    (net (code "85") (name "Net-(IC21D-O)") (class "Default")
      (node (ref "IC2") (pin "11") (pinfunction "CLK_11") (pintype "input"))
      (node (ref "IC21") (pin "11") (pinfunction "O_11") (pintype "output"))
    )
    (net (code "86") (name "PROT") (class "Default")
      (node (ref "JP10") (pin "21") (pinfunction "21_21") (pintype "passive"))
    )
    (net (code "87") (name "RBUS0") (class "Default")
      (node (ref "IC12") (pin "2") (pinfunction "1Q_2") (pintype "tri_state"))
      (node (ref "IC7") (pin "2") (pinfunction "1Q_2") (pintype "tri_state"))
      (node (ref "JP4") (pin "1") (pinfunction "1_1") (pintype "passive"))
    )
    (net (code "88") (name "RBUS1") (class "Default")
      (node (ref "IC12") (pin "5") (pinfunction "2Q_5") (pintype "tri_state"))
      (node (ref "IC7") (pin "5") (pinfunction "2Q_5") (pintype "tri_state"))
      (node (ref "JP4") (pin "2") (pinfunction "2_2") (pintype "passive"))
    )
    (net (code "89") (name "RBUS2") (class "Default")
      (node (ref "IC12") (pin "6") (pinfunction "3Q_6") (pintype "tri_state"))
      (node (ref "IC7") (pin "6") (pinfunction "3Q_6") (pintype "tri_state"))
      (node (ref "JP4") (pin "3") (pinfunction "3_3") (pintype "passive"))
    )
    (net (code "90") (name "RBUS3") (class "Default")
      (node (ref "IC12") (pin "9") (pinfunction "4Q_9") (pintype "tri_state"))
      (node (ref "IC7") (pin "9") (pinfunction "4Q_9") (pintype "tri_state"))
      (node (ref "JP4") (pin "4") (pinfunction "4_4") (pintype "passive"))
    )
    (net (code "91") (name "RBUS4") (class "Default")
      (node (ref "IC12") (pin "12") (pinfunction "5Q_12") (pintype "tri_state"))
      (node (ref "IC7") (pin "12") (pinfunction "5Q_12") (pintype "tri_state"))
      (node (ref "JP4") (pin "5") (pinfunction "5_5") (pintype "passive"))
    )
    (net (code "92") (name "RBUS5") (class "Default")
      (node (ref "IC12") (pin "15") (pinfunction "6Q_15") (pintype "tri_state"))
      (node (ref "IC7") (pin "15") (pinfunction "6Q_15") (pintype "tri_state"))
      (node (ref "JP4") (pin "6") (pinfunction "6_6") (pintype "passive"))
    )
    (net (code "93") (name "RBUS6") (class "Default")
      (node (ref "IC12") (pin "16") (pinfunction "7Q_16") (pintype "tri_state"))
      (node (ref "IC7") (pin "16") (pinfunction "7Q_16") (pintype "tri_state"))
      (node (ref "JP4") (pin "7") (pinfunction "7_7") (pintype "passive"))
    )
    (net (code "94") (name "RBUS7") (class "Default")
      (node (ref "IC12") (pin "19") (pinfunction "8Q_19") (pintype "tri_state"))
      (node (ref "IC7") (pin "19") (pinfunction "8Q_19") (pintype "tri_state"))
      (node (ref "JP4") (pin "8") (pinfunction "8_8") (pintype "passive"))
    )
    (net (code "95") (name "RBUS8") (class "Default")
      (node (ref "IC14") (pin "2") (pinfunction "1Q_2") (pintype "tri_state"))
      (node (ref "IC8") (pin "2") (pinfunction "1Q_2") (pintype "tri_state"))
      (node (ref "JP4") (pin "9") (pinfunction "9_9") (pintype "passive"))
    )
    (net (code "96") (name "RBUS9") (class "Default")
      (node (ref "IC14") (pin "5") (pinfunction "2Q_5") (pintype "tri_state"))
      (node (ref "IC8") (pin "5") (pinfunction "2Q_5") (pintype "tri_state"))
      (node (ref "JP4") (pin "10") (pinfunction "10_10") (pintype "passive"))
    )
    (net (code "97") (name "RBUS10") (class "Default")
      (node (ref "IC14") (pin "6") (pinfunction "3Q_6") (pintype "tri_state"))
      (node (ref "IC8") (pin "6") (pinfunction "3Q_6") (pintype "tri_state"))
      (node (ref "JP4") (pin "11") (pinfunction "11_11") (pintype "passive"))
    )
    (net (code "98") (name "RBUS11") (class "Default")
      (node (ref "IC14") (pin "9") (pinfunction "4Q_9") (pintype "tri_state"))
      (node (ref "IC8") (pin "9") (pinfunction "4Q_9") (pintype "tri_state"))
      (node (ref "JP4") (pin "12") (pinfunction "12_12") (pintype "passive"))
    )
    (net (code "99") (name "RBUS12") (class "Default")
      (node (ref "IC14") (pin "12") (pinfunction "5Q_12") (pintype "tri_state"))
      (node (ref "IC8") (pin "12") (pinfunction "5Q_12") (pintype "tri_state"))
      (node (ref "JP4") (pin "13") (pinfunction "13_13") (pintype "passive"))
    )
    (net (code "100") (name "RBUS13") (class "Default")
      (node (ref "IC14") (pin "15") (pinfunction "6Q_15") (pintype "tri_state"))
      (node (ref "IC8") (pin "15") (pinfunction "6Q_15") (pintype "tri_state"))
      (node (ref "JP4") (pin "14") (pinfunction "14_14") (pintype "passive"))
    )
    (net (code "101") (name "RBUS14") (class "Default")
      (node (ref "IC14") (pin "16") (pinfunction "7Q_16") (pintype "tri_state"))
      (node (ref "IC8") (pin "16") (pinfunction "7Q_16") (pintype "tri_state"))
      (node (ref "JP4") (pin "15") (pinfunction "15_15") (pintype "passive"))
    )
    (net (code "102") (name "RBUS15") (class "Default")
      (node (ref "IC14") (pin "19") (pinfunction "8Q_19") (pintype "tri_state"))
      (node (ref "IC8") (pin "19") (pinfunction "8Q_19") (pintype "tri_state"))
      (node (ref "JP4") (pin "16") (pinfunction "16_16") (pintype "passive"))
    )
    (net (code "103") (name "RST") (class "Default")
      (node (ref "JP10") (pin "9") (pinfunction "9_9") (pintype "passive"))
    )
    (net (code "104") (name "SP_DIR") (class "Default")
      (node (ref "JP10") (pin "20") (pinfunction "20_20") (pintype "passive"))
    )
    (net (code "105") (name "unconnected-(IC22C-O-Pad8)") (class "Default")
      (node (ref "IC22") (pin "8") (pinfunction "O_8") (pintype "output"))
    )
    (net (code "106") (name "unconnected-(IC22D-O-Pad11)") (class "Default")
      (node (ref "IC22") (pin "11") (pinfunction "O_11") (pintype "output"))
    )
    (net (code "107") (name "unconnected-(JP9-Pad15)") (class "Default")
      (node (ref "JP9") (pin "15") (pinfunction "15_15") (pintype "passive"))
    )
    (net (code "108") (name "unconnected-(JP9-Pad28)") (class "Default")
      (node (ref "JP9") (pin "28") (pinfunction "28_28") (pintype "passive"))
    )
    (net (code "109") (name "unconnected-(JP9-Pad30)") (class "Default")
      (node (ref "JP9") (pin "30") (pinfunction "30_30") (pintype "passive"))
    )
    (net (code "110") (name "{slash}ALUCARRYIN") (class "Default")
      (node (ref "JP9") (pin "2") (pinfunction "2_2") (pintype "passive"))
    )
    (net (code "111") (name "{slash}ALUHI2MEM") (class "Default")
      (node (ref "JP10") (pin "25") (pinfunction "25_25") (pintype "passive"))
    )
    (net (code "112") (name "{slash}ALULO2MEM") (class "Default")
      (node (ref "JP10") (pin "29") (pinfunction "29_29") (pintype "passive"))
    )
    (net (code "113") (name "{slash}ALUSHR") (class "Default")
      (node (ref "JP9") (pin "1") (pinfunction "1_1") (pintype "passive"))
    )
    (net (code "114") (name "{slash}BUSIFCEN") (class "Default")
      (node (ref "JP10") (pin "5") (pinfunction "5_5") (pintype "passive"))
    )
    (net (code "115") (name "{slash}CARRY1") (class "Default")
      (node (ref "JP9") (pin "29") (pinfunction "29_29") (pintype "passive"))
    )
    (net (code "116") (name "{slash}CARRY3") (class "Default")
      (node (ref "JP9") (pin "31") (pinfunction "31_31") (pintype "passive"))
    )
    (net (code "117") (name "{slash}CNTSP") (class "Default")
      (node (ref "JP10") (pin "3") (pinfunction "3_3") (pintype "passive"))
    )
    (net (code "118") (name "{slash}ENA") (class "Default")
      (node (ref "IC1") (pin "1") (pinfunction "OC_1") (pintype "input"))
      (node (ref "IC2") (pin "1") (pinfunction "OC_1") (pintype "input"))
      (node (ref "JP9") (pin "33") (pinfunction "33_33") (pintype "passive"))
    )
    (net (code "119") (name "{slash}ENABUS") (class "Default")
      (node (ref "JP10") (pin "22") (pinfunction "22_22") (pintype "passive"))
    )
    (net (code "120") (name "{slash}ENALU") (class "Default")
      (node (ref "JP9") (pin "39") (pinfunction "39_39") (pintype "passive"))
    )
    (net (code "121") (name "{slash}ENDP") (class "Default")
      (node (ref "IC10") (pin "1") (pinfunction "OC_1") (pintype "input"))
      (node (ref "IC9") (pin "1") (pinfunction "OC_1") (pintype "input"))
      (node (ref "JP9") (pin "44") (pinfunction "44_44") (pintype "passive"))
    )
    (net (code "122") (name "{slash}ENIPTR") (class "Default")
      (node (ref "JP9") (pin "38") (pinfunction "38_38") (pintype "passive"))
    )
    (net (code "123") (name "{slash}ENLMDR") (class "Default")
      (node (ref "IC11") (pin "1") (pinfunction "OC_1") (pintype "input"))
      (node (ref "IC13") (pin "1") (pinfunction "OC_1") (pintype "input"))
      (node (ref "JP9") (pin "34") (pinfunction "34_34") (pintype "passive"))
    )
    (net (code "124") (name "{slash}ENMAR") (class "Default")
      (node (ref "JP9") (pin "48") (pinfunction "48_48") (pintype "passive"))
    )
    (net (code "125") (name "{slash}ENMEM") (class "Default")
      (node (ref "JP10") (pin "16") (pinfunction "16_16") (pintype "passive"))
    )
    (net (code "126") (name "{slash}ENMSW") (class "Default")
      (node (ref "JP9") (pin "40") (pinfunction "40_40") (pintype "passive"))
    )
    (net (code "127") (name "{slash}ENPC") (class "Default")
      (node (ref "JP9") (pin "42") (pinfunction "42_42") (pintype "passive"))
    )
    (net (code "128") (name "{slash}ENPPC") (class "Default")
      (node (ref "IC7") (pin "1") (pinfunction "OC_1") (pintype "input"))
      (node (ref "IC8") (pin "1") (pinfunction "OC_1") (pintype "input"))
      (node (ref "JP9") (pin "37") (pinfunction "37_37") (pintype "passive"))
    )
    (net (code "129") (name "{slash}ENRMDR") (class "Default")
      (node (ref "IC12") (pin "1") (pinfunction "OC_1") (pintype "input"))
      (node (ref "IC14") (pin "1") (pinfunction "OC_1") (pintype "input"))
      (node (ref "JP9") (pin "41") (pinfunction "41_41") (pintype "passive"))
    )
    (net (code "130") (name "{slash}ENSP") (class "Default")
      (node (ref "JP9") (pin "46") (pinfunction "46_46") (pintype "passive"))
    )
    (net (code "131") (name "{slash}ENX") (class "Default")
      (node (ref "IC3") (pin "1") (pinfunction "OC_1") (pintype "input"))
      (node (ref "IC4") (pin "1") (pinfunction "OC_1") (pintype "input"))
      (node (ref "JP9") (pin "36") (pinfunction "36_36") (pintype "passive"))
    )
    (net (code "132") (name "{slash}ENY") (class "Default")
      (node (ref "IC5") (pin "1") (pinfunction "OC_1") (pintype "input"))
      (node (ref "IC6") (pin "1") (pinfunction "OC_1") (pintype "input"))
      (node (ref "JP9") (pin "35") (pinfunction "35_35") (pintype "passive"))
    )
    (net (code "133") (name "{slash}FI") (class "Default")
      (node (ref "JP10") (pin "32") (pinfunction "32_32") (pintype "passive"))
    )
    (net (code "134") (name "{slash}FS") (class "Default")
      (node (ref "JP10") (pin "30") (pinfunction "30_30") (pintype "passive"))
    )
    (net (code "135") (name "{slash}INCPC") (class "Default")
      (node (ref "JP10") (pin "1") (pinfunction "1_1") (pintype "passive"))
    )
    (net (code "136") (name "{slash}INC_MAR") (class "Default")
      (node (ref "JP9") (pin "32") (pinfunction "32_32") (pintype "passive"))
    )
    (net (code "137") (name "{slash}LATCHFLAGS") (class "Default")
      (node (ref "JP10") (pin "12") (pinfunction "12_12") (pintype "passive"))
    )
    (net (code "138") (name "{slash}LATCH_I") (class "Default")
      (node (ref "JP9") (pin "47") (pinfunction "47_47") (pintype "passive"))
    )
    (net (code "139") (name "{slash}LATCH_S") (class "Default")
      (node (ref "JP9") (pin "45") (pinfunction "45_45") (pintype "passive"))
    )
    (net (code "140") (name "{slash}LDA") (class "Default")
      (node (ref "IC21") (pin "10") (pinfunction "I1_10") (pintype "input"))
      (node (ref "IC21") (pin "13") (pinfunction "I1_13") (pintype "input"))
      (node (ref "JP9") (pin "14") (pinfunction "14_14") (pintype "passive"))
    )
    (net (code "141") (name "{slash}LDAHI") (class "Default")
      (node (ref "IC21") (pin "12") (pinfunction "I0_12") (pintype "input"))
      (node (ref "JP9") (pin "11") (pinfunction "11_11") (pintype "passive"))
    )
    (net (code "142") (name "{slash}LDALO") (class "Default")
      (node (ref "IC21") (pin "9") (pinfunction "I0_9") (pintype "input"))
      (node (ref "JP9") (pin "12") (pinfunction "12_12") (pintype "passive"))
    )
    (net (code "143") (name "{slash}LDDP") (class "Default")
      (node (ref "IC10") (pin "11") (pinfunction "CLK_11") (pintype "input"))
      (node (ref "IC9") (pin "11") (pinfunction "CLK_11") (pintype "input"))
      (node (ref "JP9") (pin "22") (pinfunction "22_22") (pintype "passive"))
    )
    (net (code "144") (name "{slash}LDMAR") (class "Default")
      (node (ref "JP9") (pin "23") (pinfunction "23_23") (pintype "passive"))
    )
    (net (code "145") (name "{slash}LDMARHI") (class "Default")
      (node (ref "JP9") (pin "17") (pinfunction "17_17") (pintype "passive"))
    )
    (net (code "146") (name "{slash}LDMARLO") (class "Default")
      (node (ref "JP9") (pin "18") (pinfunction "18_18") (pintype "passive"))
    )
    (net (code "147") (name "{slash}LDMDR") (class "Default")
      (node (ref "IC21") (pin "1") (pinfunction "I0_1") (pintype "input"))
      (node (ref "IC21") (pin "4") (pinfunction "I0_4") (pintype "input"))
      (node (ref "JP9") (pin "9") (pinfunction "9_9") (pintype "passive"))
    )
    (net (code "148") (name "{slash}LDMDRHI") (class "Default")
      (node (ref "IC21") (pin "5") (pinfunction "I1_5") (pintype "input"))
      (node (ref "JP9") (pin "10") (pinfunction "10_10") (pintype "passive"))
    )
    (net (code "149") (name "{slash}LDMDRLO") (class "Default")
      (node (ref "IC21") (pin "2") (pinfunction "I1_2") (pintype "input"))
      (node (ref "JP9") (pin "7") (pinfunction "7_7") (pintype "passive"))
    )
    (net (code "150") (name "{slash}LDMEM") (class "Default")
      (node (ref "JP10") (pin "15") (pinfunction "15_15") (pintype "passive"))
    )
    (net (code "151") (name "{slash}LDMSW") (class "Default")
      (node (ref "JP9") (pin "20") (pinfunction "20_20") (pintype "passive"))
    )
    (net (code "152") (name "{slash}LDPC") (class "Default")
      (node (ref "JP9") (pin "19") (pinfunction "19_19") (pintype "passive"))
    )
    (net (code "153") (name "{slash}LDPPC") (class "Default")
      (node (ref "IC7") (pin "11") (pinfunction "CLK_11") (pintype "input"))
      (node (ref "IC8") (pin "11") (pinfunction "CLK_11") (pintype "input"))
      (node (ref "JP10") (pin "11") (pinfunction "11_11") (pintype "passive"))
    )
    (net (code "154") (name "{slash}LDSP") (class "Default")
      (node (ref "JP9") (pin "21") (pinfunction "21_21") (pintype "passive"))
    )
    (net (code "155") (name "{slash}LDX") (class "Default")
      (node (ref "IC3") (pin "11") (pinfunction "CLK_11") (pintype "input"))
      (node (ref "IC4") (pin "11") (pinfunction "CLK_11") (pintype "input"))
      (node (ref "JP9") (pin "13") (pinfunction "13_13") (pintype "passive"))
    )
    (net (code "156") (name "{slash}LDY") (class "Default")
      (node (ref "IC5") (pin "11") (pinfunction "CLK_11") (pintype "input"))
      (node (ref "IC6") (pin "11") (pinfunction "CLK_11") (pintype "input"))
      (node (ref "JP9") (pin "16") (pinfunction "16_16") (pintype "passive"))
    )
    (net (code "157") (name "{slash}LOAD_IR") (class "Default")
      (node (ref "JP10") (pin "26") (pinfunction "26_26") (pintype "passive"))
    )
    (net (code "158") (name "{slash}MEM2ALUHI") (class "Default")
      (node (ref "JP10") (pin "27") (pinfunction "27_27") (pintype "passive"))
    )
    (net (code "159") (name "{slash}MEM2ALULO") (class "Default")
      (node (ref "JP10") (pin "31") (pinfunction "31_31") (pintype "passive"))
    )
    (net (code "160") (name "{slash}RST") (class "Default")
      (node (ref "JP10") (pin "7") (pinfunction "7_7") (pintype "passive"))
    )
  )
)
